# ADCin.net
KiCad netlist of a schematic drawn in Altium Designer
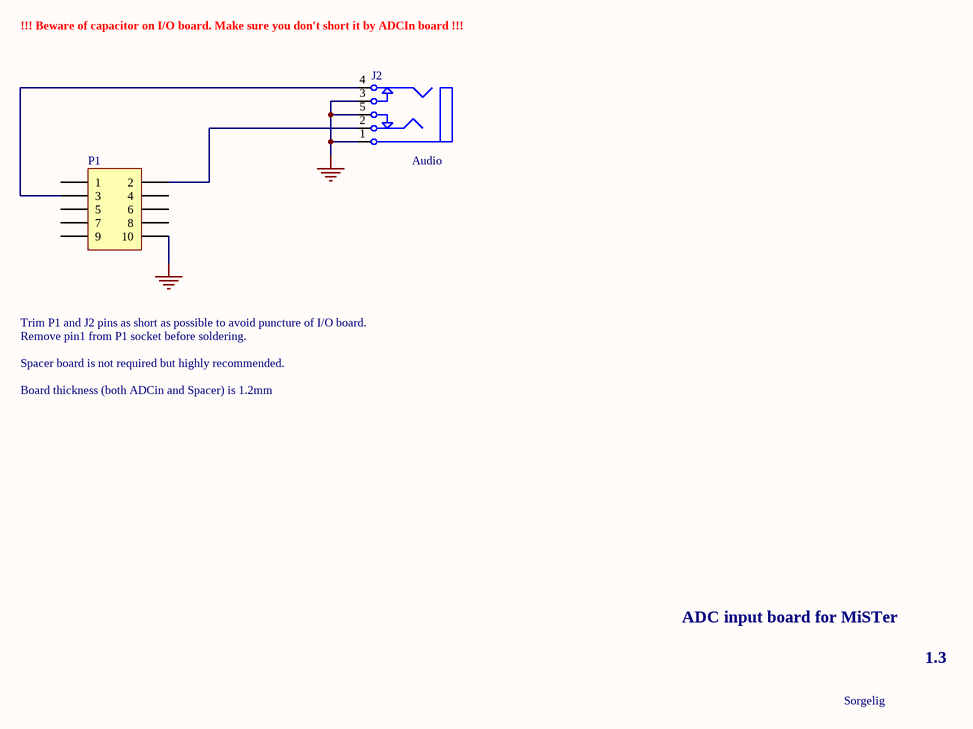
[diagram p0: ADCin.SchDoc]

(export (version "E")
  (design (tool "Eeschema 10.0.6"))
  (components
    (comp (ref "J2") (value "Audio") (footprint "phonejack") (libsource (lib "lib") (part "phonejack")))
    (comp (ref "P1")
      (value "Header 5X2")
      (footprint "HDR2X5")
      (description "Header, 5-Pin, Dual row")
      (fields (field (name "PUBLISHER") "Altium Limited"))
      (libsource (lib "Miscellaneous Connectors") (part "Header 5X2"))
    )
  )
  (nets
    (net (code "1") (name "GND") (class "Default")
      (node (ref "J2") (pin "1") (pinfunction "1_1") (pintype "passive"))
      (node (ref "J2") (pin "3") (pinfunction "3_3") (pintype "passive"))
      (node (ref "J2") (pin "5") (pinfunction "5_5") (pintype "passive"))
      (node (ref "P1") (pin "10") (pinfunction "10_10") (pintype "passive"))
    )
    (net (code "2") (name "Net-(J2-Pad2)") (class "Default")
      (node (ref "J2") (pin "2") (pinfunction "2_2") (pintype "passive"))
      (node (ref "P1") (pin "2") (pinfunction "2_2") (pintype "passive"))
    )
    (net (code "3") (name "Net-(J2-Pad4)") (class "Default")
      (node (ref "J2") (pin "4") (pinfunction "4_4") (pintype "passive"))
      (node (ref "P1") (pin "3") (pinfunction "3_3") (pintype "passive"))
    )
    (net (code "4") (name "unconnected-(P1-Pad1)") (class "Default")
      (node (ref "P1") (pin "1") (pinfunction "1_1") (pintype "passive"))
    )
    (net (code "5") (name "unconnected-(P1-Pad4)") (class "Default")
      (node (ref "P1") (pin "4") (pinfunction "4_4") (pintype "passive"))
    )
    (net (code "6") (name "unconnected-(P1-Pad5)") (class "Default")
      (node (ref "P1") (pin "5") (pinfunction "5_5") (pintype "passive"))
    )
    (net (code "7") (name "unconnected-(P1-Pad6)") (class "Default")
      (node (ref "P1") (pin "6") (pinfunction "6_6") (pintype "passive"))
    )
    (net (code "8") (name "unconnected-(P1-Pad7)") (class "Default")
      (node (ref "P1") (pin "7") (pinfunction "7_7") (pintype "passive"))
    )
    (net (code "9") (name "unconnected-(P1-Pad8)") (class "Default")
      (node (ref "P1") (pin "8") (pinfunction "8_8") (pintype "passive"))
    )
    (net (code "10") (name "unconnected-(P1-Pad9)") (class "Default")
      (node (ref "P1") (pin "9") (pinfunction "9_9") (pintype "passive"))
    )
  )
)
